# WeatherReportR03.net
KiCad netlist of a schematic drawn in EAGLE
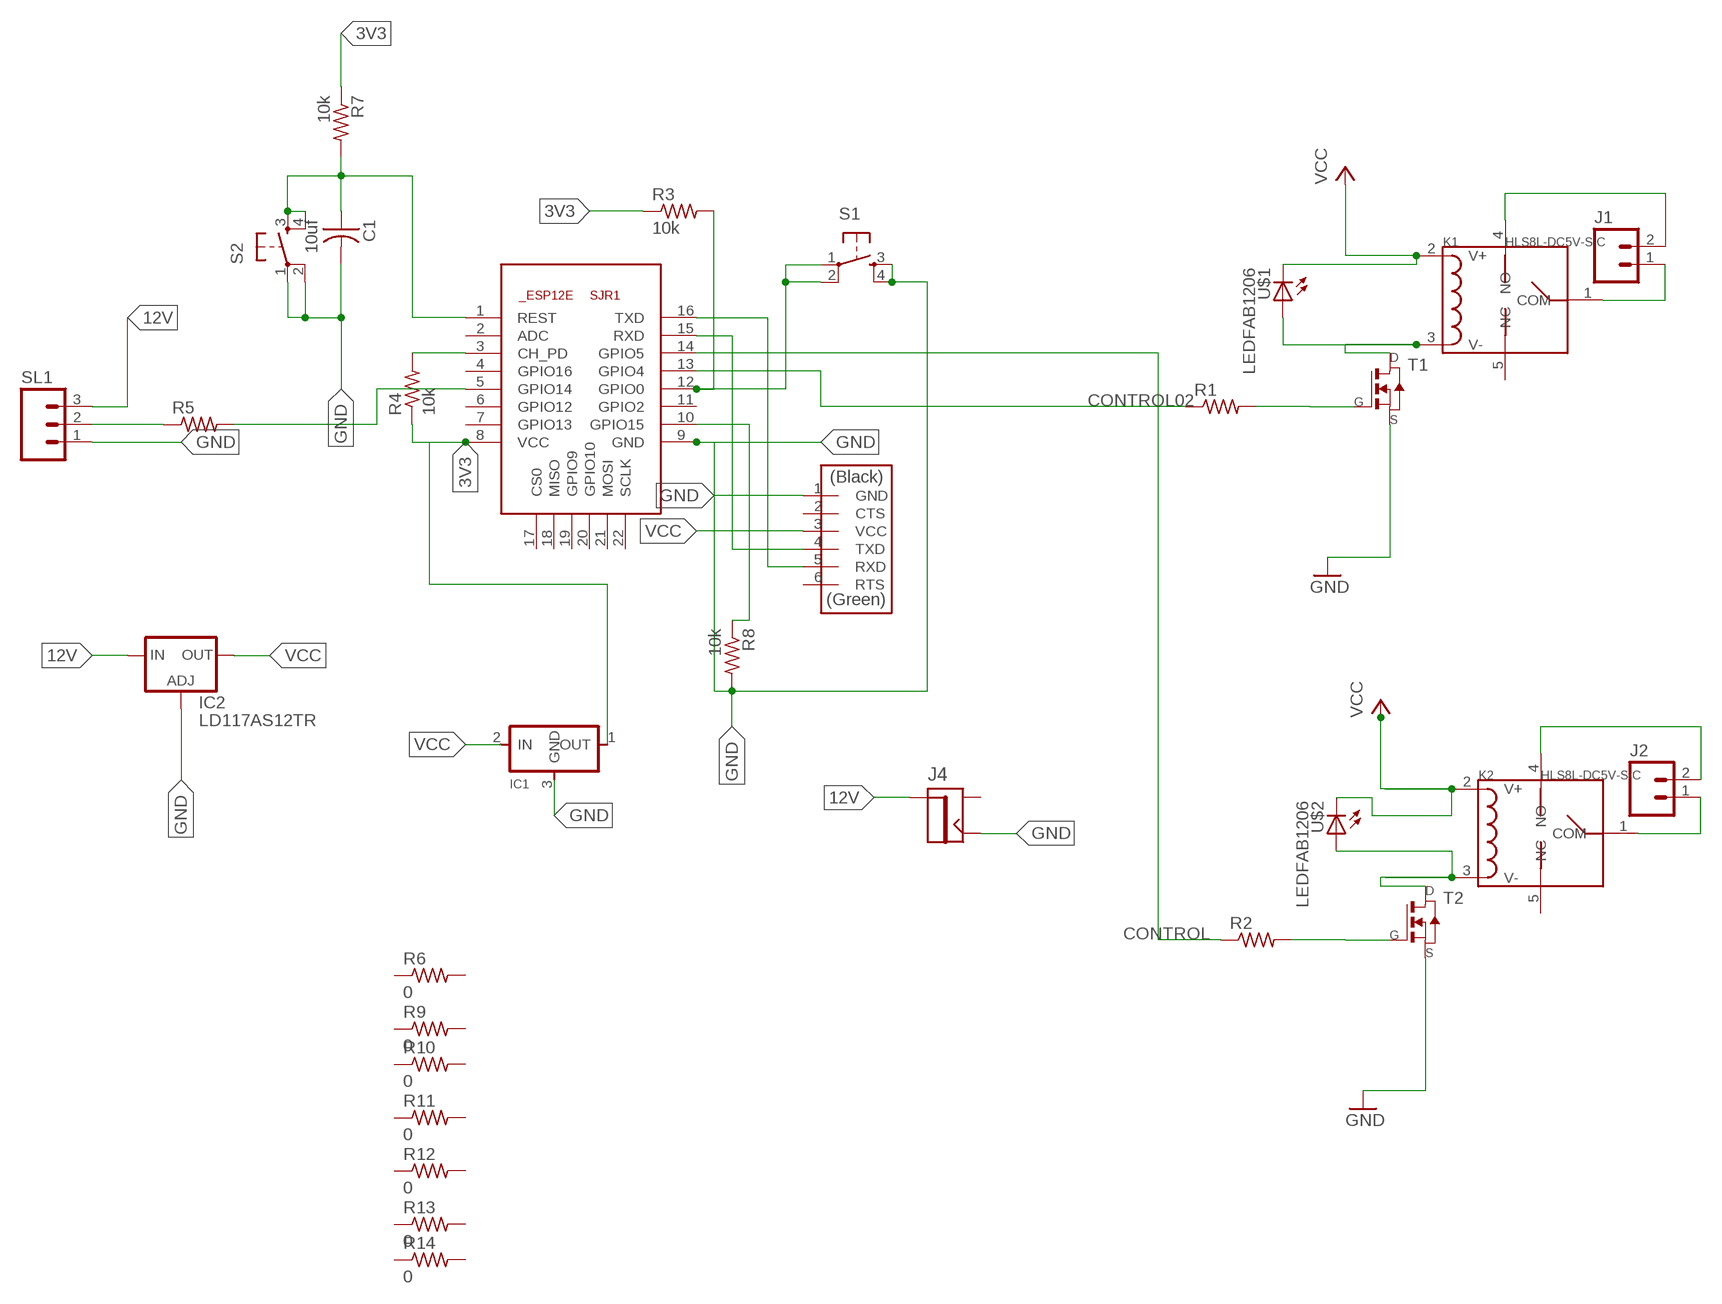
[diagram p0: schematic, sheet 1]

(export (version "E")
  (design (tool "Eeschema 10.0.6"))
  (components
    (comp (ref "C1")
      (value "10uf")
      (footprint "eagle-import:C1206FAB")
      (libsource (lib "eagle-import") (part "CAP-US1206FAB"))
    )
    (comp (ref "IC1")
      (value "REGULATORSOT23")
      (footprint "eagle-import:SOT23")
      (libsource (lib "eagle-import") (part "REGULATORSOT23"))
    )
    (comp (ref "IC2")
      (value "LD117AS12TR")
      (footprint "eagle-import:SOT223")
      (libsource (lib "eagle-import") (part "LD117A?S12TR"))
    )
    (comp (ref "J1")
      (value "M02POLAR_LOCK")
      (footprint "eagle-import:MOLEX-1X2_LOCK")
      (libsource (lib "eagle-import") (part "M02POLAR_LOCK"))
    )
    (comp (ref "J2")
      (value "M02POLAR_LOCK")
      (footprint "eagle-import:MOLEX-1X2_LOCK")
      (libsource (lib "eagle-import") (part "M02POLAR_LOCK"))
    )
    (comp (ref "J4")
      (value "JACK2.1MM")
      (footprint "eagle-import:JACK_2.1MM")
      (libsource (lib "eagle-import") (part "JACK2.1MM"))
    )
    (comp (ref "K1")
      (value "HLS8L-DC5V-S-C")
      (footprint "eagle-import:REY5-19.0X15.0X15.0MM")
      (libsource (lib "eagle-import") (part "RELAY-HLS8L-DC5V-S-C(5P-19X15MM)"))
    )
    (comp (ref "K2")
      (value "HLS8L-DC5V-S-C")
      (footprint "eagle-import:REY5-19.0X15.0X15.0MM")
      (libsource (lib "eagle-import") (part "RELAY-HLS8L-DC5V-S-C(5P-19X15MM)"))
    )
    (comp (ref "R1")
      (value "RES-US1206FAB")
      (footprint "eagle-import:R1206FAB")
      (libsource (lib "eagle-import") (part "RES-US1206FAB"))
    )
    (comp (ref "R2")
      (value "RES-US1206FAB")
      (footprint "eagle-import:R1206FAB")
      (libsource (lib "eagle-import") (part "RES-US1206FAB"))
    )
    (comp (ref "R3")
      (value "10k")
      (footprint "eagle-import:R1206FAB")
      (libsource (lib "eagle-import") (part "RES-US1206FAB"))
    )
    (comp (ref "R4")
      (value "10k")
      (footprint "eagle-import:R1206FAB")
      (libsource (lib "eagle-import") (part "RES-US1206FAB"))
    )
    (comp (ref "R5")
      (value "RES-US1206FAB")
      (footprint "eagle-import:R1206FAB")
      (libsource (lib "eagle-import") (part "RES-US1206FAB"))
    )
    (comp (ref "R6")
      (value "0")
      (footprint "eagle-import:R1206FAB")
      (libsource (lib "eagle-import") (part "RES-US1206FAB"))
    )
    (comp (ref "R7")
      (value "10k")
      (footprint "eagle-import:R1206FAB")
      (libsource (lib "eagle-import") (part "RES-US1206FAB"))
    )
    (comp (ref "R8")
      (value "10k")
      (footprint "eagle-import:R1206FAB")
      (libsource (lib "eagle-import") (part "RES-US1206FAB"))
    )
    (comp (ref "R9")
      (value "0")
      (footprint "eagle-import:R1206FAB")
      (libsource (lib "eagle-import") (part "RES-US1206FAB"))
    )
    (comp (ref "R10")
      (value "0")
      (footprint "eagle-import:R1206FAB")
      (libsource (lib "eagle-import") (part "RES-US1206FAB"))
    )
    (comp (ref "R11")
      (value "0")
      (footprint "eagle-import:R1206FAB")
      (libsource (lib "eagle-import") (part "RES-US1206FAB"))
    )
    (comp (ref "R12")
      (value "0")
      (footprint "eagle-import:R1206FAB")
      (libsource (lib "eagle-import") (part "RES-US1206FAB"))
    )
    (comp (ref "R13")
      (value "0")
      (footprint "eagle-import:R1206FAB")
      (libsource (lib "eagle-import") (part "RES-US1206FAB"))
    )
    (comp (ref "R14")
      (value "0")
      (footprint "eagle-import:R1206FAB")
      (libsource (lib "eagle-import") (part "RES-US1206FAB"))
    )
    (comp (ref "S1")
      (value "6MM_SWITCH6MM_SWITCH")
      (footprint "eagle-import:6MM_SWITCH")
      (libsource (lib "eagle-import") (part "6MM_SWITCH6MM_SWITCH"))
    )
    (comp (ref "S2")
      (value "6MM_SWITCH6MM_SWITCH")
      (footprint "eagle-import:6MM_SWITCH")
      (libsource (lib "eagle-import") (part "6MM_SWITCH6MM_SWITCH"))
    )
    (comp (ref "SJR1")
      (value "ESP8266-12EESP12E")
      (footprint "eagle-import:ESP8266-ESP12E")
      (libsource (lib "eagle-import") (part "ESP8266-12EESP12E"))
    )
    (comp (ref "SL1")
      (value "M03")
      (footprint "eagle-import:03P")
      (libsource (lib "eagle-import") (part "M03"))
    )
    (comp (ref "T1")
      (value "NMOSFETSOT23")
      (footprint "eagle-import:SOT-23")
      (libsource (lib "eagle-import") (part "NMOSFETSOT23"))
    )
    (comp (ref "T2")
      (value "NMOSFETSOT23")
      (footprint "eagle-import:SOT-23")
      (libsource (lib "eagle-import") (part "NMOSFETSOT23"))
    )
    (comp (ref "U$1")
      (value "LEDFAB1206")
      (footprint "eagle-import:LED1206FAB")
      (libsource (lib "eagle-import") (part "LEDFAB1206"))
    )
    (comp (ref "U$2")
      (value "LEDFAB1206")
      (footprint "eagle-import:LED1206FAB")
      (libsource (lib "eagle-import") (part "LEDFAB1206"))
    )
    (comp (ref "U$7")
      (value "FTDI-SMD-HEADER")
      (footprint "eagle-import:1X06SMD")
      (libsource (lib "eagle-import") (part "FTDI-SMD-HEADER"))
    )
  )
  (nets
    (net (code "1") (name "/CONTROL") (class "Default")
      (node (ref "R2") (pin "1") (pinfunction "1_1") (pintype "passive"))
      (node (ref "SJR1") (pin "14") (pinfunction "GPIO5_14") (pintype "bidirectional"))
    )
    (net (code "2") (name "/CONTROL02") (class "Default")
      (node (ref "R1") (pin "1") (pinfunction "1_1") (pintype "passive"))
      (node (ref "SJR1") (pin "13") (pinfunction "GPIO4_13") (pintype "bidirectional"))
    )
    (net (code "3") (name "3V3") (class "Default")
      (node (ref "IC1") (pin "1") (pinfunction "OUT_1") (pintype "bidirectional"))
      (node (ref "R3") (pin "1") (pinfunction "1_1") (pintype "passive"))
      (node (ref "R4") (pin "1") (pinfunction "1_1") (pintype "passive"))
      (node (ref "R7") (pin "1") (pinfunction "1_1") (pintype "passive"))
      (node (ref "SJR1") (pin "8") (pinfunction "VCC_8") (pintype "bidirectional"))
    )
    (net (code "4") (name "12V") (class "Default")
      (node (ref "IC2") (pin "3") (pinfunction "IN_3") (pintype "input"))
      (node (ref "J4") (pin "PIN") (pinfunction "PIN_PIN") (pintype "bidirectional"))
      (node (ref "SL1") (pin "3") (pinfunction "3_3") (pintype "passive"))
    )
    (net (code "5") (name "GND") (class "Default")
      (node (ref "C1") (pin "2") (pinfunction "2_2") (pintype "passive"))
      (node (ref "IC1") (pin "3") (pinfunction "GND_3") (pintype "bidirectional"))
      (node (ref "IC2") (pin "1") (pinfunction "ADJ_1") (pintype "input"))
      (node (ref "J4") (pin "CONTACT") (pinfunction "CONTACT_CONTACT") (pintype "bidirectional"))
      (node (ref "R8") (pin "2") (pinfunction "2_2") (pintype "passive"))
      (node (ref "S1") (pin "3") (pinfunction "S_3") (pintype "passive"))
      (node (ref "S1") (pin "4") (pinfunction "S1_4") (pintype "passive"))
      (node (ref "S2") (pin "1") (pinfunction "P_1") (pintype "passive"))
      (node (ref "S2") (pin "2") (pinfunction "P1_2") (pintype "passive"))
      (node (ref "SJR1") (pin "9") (pinfunction "GND_9") (pintype "bidirectional"))
      (node (ref "SL1") (pin "1") (pinfunction "1_1") (pintype "passive"))
      (node (ref "T1") (pin "2") (pinfunction "S_2") (pintype "passive"))
      (node (ref "T2") (pin "2") (pinfunction "S_2") (pintype "passive"))
      (node (ref "U$7") (pin "1") (pinfunction "GND_1") (pintype "bidirectional"))
    )
    (net (code "6") (name "Net-(K1-COM)") (class "Default")
      (node (ref "J1") (pin "1") (pinfunction "1_1") (pintype "passive"))
      (node (ref "K1") (pin "1") (pinfunction "COM_1") (pintype "bidirectional"))
    )
    (net (code "7") (name "Net-(K1-NO)") (class "Default")
      (node (ref "J1") (pin "2") (pinfunction "2_2") (pintype "passive"))
      (node (ref "K1") (pin "4") (pinfunction "NO_4") (pintype "bidirectional"))
    )
    (net (code "8") (name "Net-(K1-V-)") (class "Default")
      (node (ref "K1") (pin "3") (pinfunction "V-_3") (pintype "bidirectional"))
      (node (ref "T1") (pin "1") (pinfunction "D_1") (pintype "passive"))
      (node (ref "U$1") (pin "1") (pinfunction "A_1") (pintype "passive"))
    )
    (net (code "9") (name "Net-(K2-COM)") (class "Default")
      (node (ref "J2") (pin "1") (pinfunction "1_1") (pintype "passive"))
      (node (ref "K2") (pin "1") (pinfunction "COM_1") (pintype "bidirectional"))
    )
    (net (code "10") (name "Net-(K2-NO)") (class "Default")
      (node (ref "J2") (pin "2") (pinfunction "2_2") (pintype "passive"))
      (node (ref "K2") (pin "4") (pinfunction "NO_4") (pintype "bidirectional"))
    )
    (net (code "11") (name "Net-(K2-V-)") (class "Default")
      (node (ref "K2") (pin "3") (pinfunction "V-_3") (pintype "bidirectional"))
      (node (ref "T2") (pin "1") (pinfunction "D_1") (pintype "passive"))
      (node (ref "U$2") (pin "1") (pinfunction "A_1") (pintype "passive"))
    )
    (net (code "12") (name "Net-(R5-Pad1)") (class "Default")
      (node (ref "R5") (pin "1") (pinfunction "1_1") (pintype "passive"))
      (node (ref "SL1") (pin "2") (pinfunction "2_2") (pintype "passive"))
    )
    (net (code "13") (name "Net-(S1-P)") (class "Default")
      (node (ref "R3") (pin "2") (pinfunction "2_2") (pintype "passive"))
      (node (ref "S1") (pin "1") (pinfunction "P_1") (pintype "passive"))
      (node (ref "S1") (pin "2") (pinfunction "P1_2") (pintype "passive"))
      (node (ref "SJR1") (pin "12") (pinfunction "GPIO0_12") (pintype "bidirectional"))
    )
    (net (code "14") (name "Net-(S2-S)") (class "Default")
      (node (ref "C1") (pin "1") (pinfunction "1_1") (pintype "passive"))
      (node (ref "R7") (pin "2") (pinfunction "2_2") (pintype "passive"))
      (node (ref "S2") (pin "3") (pinfunction "S_3") (pintype "passive"))
      (node (ref "S2") (pin "4") (pinfunction "S1_4") (pintype "passive"))
      (node (ref "SJR1") (pin "1") (pinfunction "REST_1") (pintype "bidirectional"))
    )
    (net (code "15") (name "Net-(SJR1-CH_PD)") (class "Default")
      (node (ref "R4") (pin "2") (pinfunction "2_2") (pintype "passive"))
      (node (ref "SJR1") (pin "3") (pinfunction "CH_PD_3") (pintype "bidirectional"))
    )
    (net (code "16") (name "Net-(SJR1-GPIO14)") (class "Default")
      (node (ref "R5") (pin "2") (pinfunction "2_2") (pintype "passive"))
      (node (ref "SJR1") (pin "5") (pinfunction "GPIO14_5") (pintype "bidirectional"))
    )
    (net (code "17") (name "Net-(SJR1-GPIO15)") (class "Default")
      (node (ref "R8") (pin "1") (pinfunction "1_1") (pintype "passive"))
      (node (ref "SJR1") (pin "10") (pinfunction "GPIO15_10") (pintype "bidirectional"))
    )
    (net (code "18") (name "Net-(SJR1-RXD)") (class "Default")
      (node (ref "SJR1") (pin "15") (pinfunction "RXD_15") (pintype "bidirectional"))
      (node (ref "U$7") (pin "4") (pinfunction "TXD_4") (pintype "bidirectional"))
    )
    (net (code "19") (name "Net-(SJR1-TXD)") (class "Default")
      (node (ref "SJR1") (pin "16") (pinfunction "TXD_16") (pintype "bidirectional"))
      (node (ref "U$7") (pin "5") (pinfunction "RXD_5") (pintype "bidirectional"))
    )
    (net (code "20") (name "Net-(T1-G)") (class "Default")
      (node (ref "R1") (pin "2") (pinfunction "2_2") (pintype "passive"))
      (node (ref "T1") (pin "3") (pinfunction "G_3") (pintype "passive"))
    )
    (net (code "21") (name "Net-(T2-G)") (class "Default")
      (node (ref "R2") (pin "2") (pinfunction "2_2") (pintype "passive"))
      (node (ref "T2") (pin "3") (pinfunction "G_3") (pintype "passive"))
    )
    (net (code "22") (name "VCC") (class "Default")
      (node (ref "IC1") (pin "2") (pinfunction "IN_2") (pintype "bidirectional"))
      (node (ref "IC2") (pin "4") (pinfunction "OUT_4") (pintype "passive"))
      (node (ref "K1") (pin "2") (pinfunction "V+_2") (pintype "bidirectional"))
      (node (ref "K2") (pin "2") (pinfunction "V+_2") (pintype "bidirectional"))
      (node (ref "U$1") (pin "2") (pinfunction "C_2") (pintype "passive"))
      (node (ref "U$2") (pin "2") (pinfunction "C_2") (pintype "passive"))
      (node (ref "U$7") (pin "3") (pinfunction "VCC_3") (pintype "bidirectional"))
    )
    (net (code "23") (name "unconnected-(J4-PadSHUNT)") (class "Default")
      (node (ref "J4") (pin "SHUNT") (pinfunction "SHUNT_SHUNT") (pintype "bidirectional"))
    )
    (net (code "24") (name "unconnected-(K1-NC-Pad5)") (class "Default")
      (node (ref "K1") (pin "5") (pinfunction "NC_5") (pintype "bidirectional"))
    )
    (net (code "25") (name "unconnected-(K2-NC-Pad5)") (class "Default")
      (node (ref "K2") (pin "5") (pinfunction "NC_5") (pintype "bidirectional"))
    )
    (net (code "26") (name "unconnected-(R6-Pad1)") (class "Default")
      (node (ref "R6") (pin "1") (pinfunction "1_1") (pintype "passive"))
    )
    (net (code "27") (name "unconnected-(R6-Pad2)") (class "Default")
      (node (ref "R6") (pin "2") (pinfunction "2_2") (pintype "passive"))
    )
    (net (code "28") (name "unconnected-(R9-Pad1)") (class "Default")
      (node (ref "R9") (pin "1") (pinfunction "1_1") (pintype "passive"))
    )
    (net (code "29") (name "unconnected-(R9-Pad2)") (class "Default")
      (node (ref "R9") (pin "2") (pinfunction "2_2") (pintype "passive"))
    )
    (net (code "30") (name "unconnected-(R10-Pad1)") (class "Default")
      (node (ref "R10") (pin "1") (pinfunction "1_1") (pintype "passive"))
    )
    (net (code "31") (name "unconnected-(R10-Pad2)") (class "Default")
      (node (ref "R10") (pin "2") (pinfunction "2_2") (pintype "passive"))
    )
    (net (code "32") (name "unconnected-(R11-Pad1)") (class "Default")
      (node (ref "R11") (pin "1") (pinfunction "1_1") (pintype "passive"))
    )
    (net (code "33") (name "unconnected-(R11-Pad2)") (class "Default")
      (node (ref "R11") (pin "2") (pinfunction "2_2") (pintype "passive"))
    )
    (net (code "34") (name "unconnected-(R12-Pad1)") (class "Default")
      (node (ref "R12") (pin "1") (pinfunction "1_1") (pintype "passive"))
    )
    (net (code "35") (name "unconnected-(R12-Pad2)") (class "Default")
      (node (ref "R12") (pin "2") (pinfunction "2_2") (pintype "passive"))
    )
    (net (code "36") (name "unconnected-(R13-Pad1)") (class "Default")
      (node (ref "R13") (pin "1") (pinfunction "1_1") (pintype "passive"))
    )
    (net (code "37") (name "unconnected-(R13-Pad2)") (class "Default")
      (node (ref "R13") (pin "2") (pinfunction "2_2") (pintype "passive"))
    )
    (net (code "38") (name "unconnected-(R14-Pad1)") (class "Default")
      (node (ref "R14") (pin "1") (pinfunction "1_1") (pintype "passive"))
    )
    (net (code "39") (name "unconnected-(R14-Pad2)") (class "Default")
      (node (ref "R14") (pin "2") (pinfunction "2_2") (pintype "passive"))
    )
    (net (code "40") (name "unconnected-(SJR1-ADC-Pad2)") (class "Default")
      (node (ref "SJR1") (pin "2") (pinfunction "ADC_2") (pintype "bidirectional"))
    )
    (net (code "41") (name "unconnected-(SJR1-CS0-Pad17)") (class "Default")
      (node (ref "SJR1") (pin "17") (pinfunction "CS0_17") (pintype "bidirectional"))
    )
    (net (code "42") (name "unconnected-(SJR1-GPIO2-Pad11)") (class "Default")
      (node (ref "SJR1") (pin "11") (pinfunction "GPIO2_11") (pintype "bidirectional"))
    )
    (net (code "43") (name "unconnected-(SJR1-GPIO9-Pad19)") (class "Default")
      (node (ref "SJR1") (pin "19") (pinfunction "GPIO9_19") (pintype "bidirectional"))
    )
    (net (code "44") (name "unconnected-(SJR1-GPIO10-Pad20)") (class "Default")
      (node (ref "SJR1") (pin "20") (pinfunction "GPIO10_20") (pintype "bidirectional"))
    )
    (net (code "45") (name "unconnected-(SJR1-GPIO12-Pad6)") (class "Default")
      (node (ref "SJR1") (pin "6") (pinfunction "GPIO12_6") (pintype "bidirectional"))
    )
    (net (code "46") (name "unconnected-(SJR1-GPIO13-Pad7)") (class "Default")
      (node (ref "SJR1") (pin "7") (pinfunction "GPIO13_7") (pintype "bidirectional"))
    )
    (net (code "47") (name "unconnected-(SJR1-GPIO16-Pad4)") (class "Default")
      (node (ref "SJR1") (pin "4") (pinfunction "GPIO16_4") (pintype "bidirectional"))
    )
    (net (code "48") (name "unconnected-(SJR1-MISO-Pad18)") (class "Default")
      (node (ref "SJR1") (pin "18") (pinfunction "MISO_18") (pintype "bidirectional"))
    )
    (net (code "49") (name "unconnected-(SJR1-MOSI-Pad21)") (class "Default")
      (node (ref "SJR1") (pin "21") (pinfunction "MOSI_21") (pintype "bidirectional"))
    )
    (net (code "50") (name "unconnected-(SJR1-SCLK-Pad22)") (class "Default")
      (node (ref "SJR1") (pin "22") (pinfunction "SCLK_22") (pintype "bidirectional"))
    )
    (net (code "51") (name "unconnected-(U$7-CTS-Pad2)") (class "Default")
      (node (ref "U$7") (pin "2") (pinfunction "CTS_2") (pintype "bidirectional"))
    )
    (net (code "52") (name "unconnected-(U$7-RTS-Pad6)") (class "Default")
      (node (ref "U$7") (pin "6") (pinfunction "RTS_6") (pintype "bidirectional"))
    )
  )
)
